# Solder_Paste_Controller.net
KiCad netlist of a schematic drawn in EAGLE
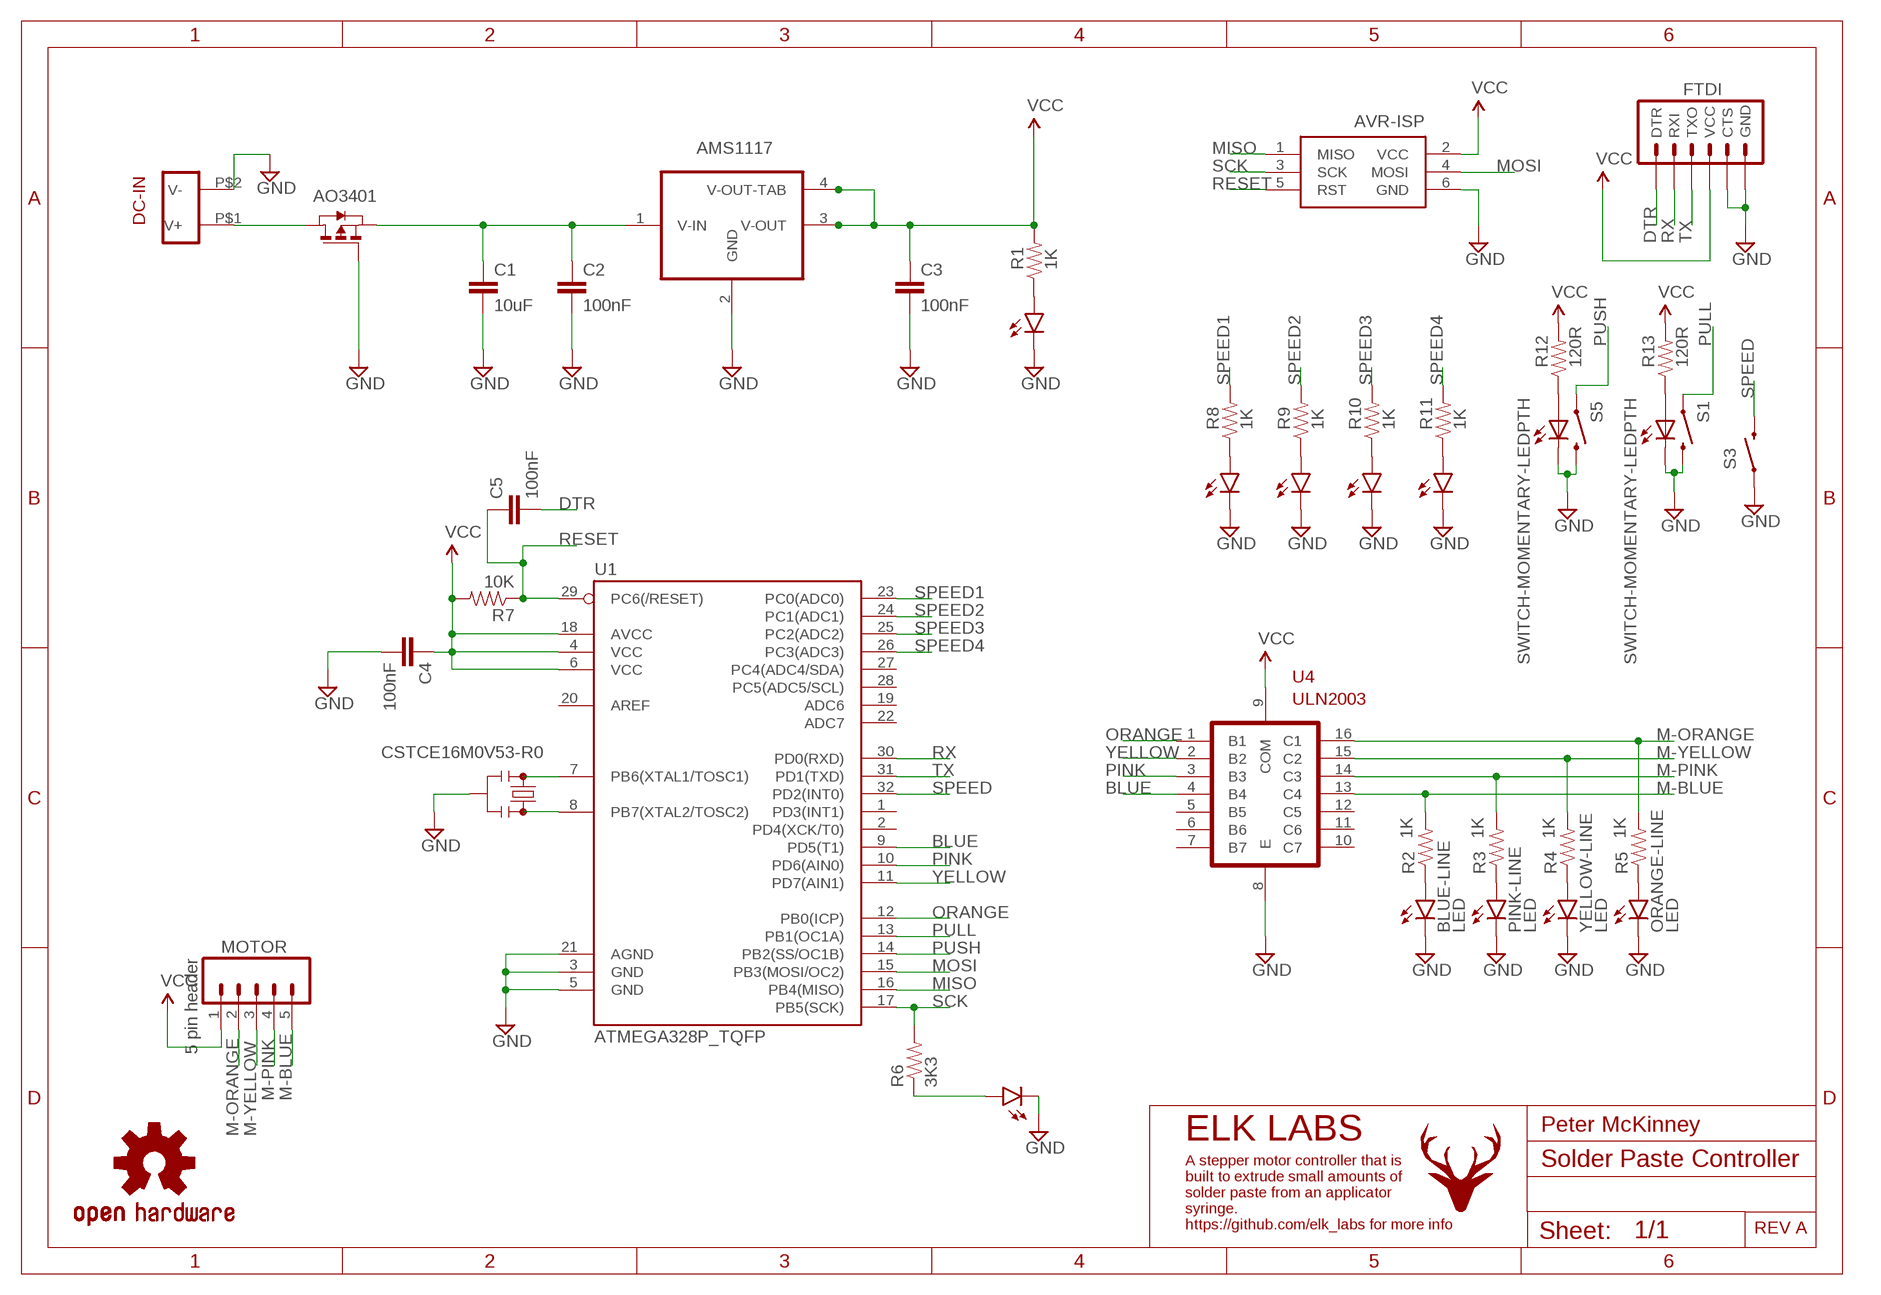
[diagram p0: schematic, sheet 1]

(export (version "E")
  (design (tool "Eeschema 10.0.6"))
  (components
    (comp (ref "AVR-ISP")
      (value "AVRISP-6")
      (footprint "eagle-import:AVRISP")
      (libsource (lib "eagle-import") (part "AVRISP-6"))
    )
    (comp (ref "BLUE-LINE")
      (value "LED")
      (footprint "eagle-import:0805-LED")
      (libsource (lib "eagle-import") (part "LED"))
    )
    (comp (ref "C1")
      (value "10uF")
      (footprint "eagle-import:0805")
      (libsource (lib "eagle-import") (part "1UF-25V-10%(0805)"))
    )
    (comp (ref "C2")
      (value "100nF")
      (footprint "eagle-import:0805")
      (libsource (lib "eagle-import") (part "1UF-25V-10%(0805)"))
    )
    (comp (ref "C3")
      (value "100nF")
      (footprint "eagle-import:0805")
      (libsource (lib "eagle-import") (part "1UF-25V-10%(0805)"))
    )
    (comp (ref "C4")
      (value "100nF")
      (footprint "eagle-import:0805")
      (libsource (lib "eagle-import") (part "1UF-25V-10%(0805)"))
    )
    (comp (ref "C5")
      (value "100nF")
      (footprint "eagle-import:0805")
      (libsource (lib "eagle-import") (part "1UF-25V-10%(0805)"))
    )
    (comp (ref "CRYSTAL")
      (value "CSTCE16M0V53-R0")
      (footprint "eagle-import:CSTCE_V")
      (libsource (lib "eagle-import") (part "CSTCE16M0V53-R0"))
    )
    (comp (ref "DC-IN")
      (value "red black twister wire")
      (footprint "eagle-import:POWER_CONNECTOR_WITH_RELIEF")
      (libsource (lib "eagle-import") (part "POWER-IN-WITH-RELIEF"))
    )
    (comp (ref "FTDI")
      (value "6 pin header")
      (footprint "eagle-import:1X06")
      (libsource (lib "eagle-import") (part "ARDUINO_SERIAL_PROGRAMPTH"))
    )
    (comp (ref "HEARTBEAT")
      (value "LED")
      (footprint "eagle-import:0805-LED")
      (libsource (lib "eagle-import") (part "LED"))
    )
    (comp (ref "LOGO1")
      (value "OSHW-LOGOS")
      (footprint "eagle-import:OSHW-LOGO-S")
      (libsource (lib "eagle-import") (part "OSHW-LOGOS"))
    )
    (comp (ref "MOTOR")
      (value "5 pin header")
      (footprint "eagle-import:1X05")
      (libsource (lib "eagle-import") (part "M05PTH"))
    )
    (comp (ref "ORANGE-LINE")
      (value "LED")
      (footprint "eagle-import:0805-LED")
      (libsource (lib "eagle-import") (part "LED"))
    )
    (comp (ref "PINK-LINE")
      (value "LED")
      (footprint "eagle-import:0805-LED")
      (libsource (lib "eagle-import") (part "LED"))
    )
    (comp (ref "PWRLED")
      (value "LED")
      (footprint "eagle-import:0805-LED")
      (libsource (lib "eagle-import") (part "LED"))
    )
    (comp (ref "R1")
      (value "1K")
      (footprint "eagle-import:0805")
      (libsource (lib "eagle-import") (part "RESISTOR0805-RES"))
    )
    (comp (ref "R2")
      (value "1K")
      (footprint "eagle-import:0805")
      (libsource (lib "eagle-import") (part "RESISTOR0805-RES"))
    )
    (comp (ref "R3")
      (value "1K")
      (footprint "eagle-import:0805")
      (libsource (lib "eagle-import") (part "RESISTOR0805-RES"))
    )
    (comp (ref "R4")
      (value "1K")
      (footprint "eagle-import:0805")
      (libsource (lib "eagle-import") (part "RESISTOR0805-RES"))
    )
    (comp (ref "R5")
      (value "1K")
      (footprint "eagle-import:0805")
      (libsource (lib "eagle-import") (part "RESISTOR0805-RES"))
    )
    (comp (ref "R6")
      (value "3K3")
      (footprint "eagle-import:0805")
      (libsource (lib "eagle-import") (part "RESISTOR0805-RES"))
    )
    (comp (ref "R7")
      (value "10K")
      (footprint "eagle-import:0805")
      (libsource (lib "eagle-import") (part "RESISTOR0805-RES"))
    )
    (comp (ref "R8")
      (value "1K")
      (footprint "eagle-import:0805")
      (libsource (lib "eagle-import") (part "RESISTOR0805-RES"))
    )
    (comp (ref "R9")
      (value "1K")
      (footprint "eagle-import:0805")
      (libsource (lib "eagle-import") (part "RESISTOR0805-RES"))
    )
    (comp (ref "R10")
      (value "1K")
      (footprint "eagle-import:0805")
      (libsource (lib "eagle-import") (part "RESISTOR0805-RES"))
    )
    (comp (ref "R11")
      (value "1K")
      (footprint "eagle-import:0805")
      (libsource (lib "eagle-import") (part "RESISTOR0805-RES"))
    )
    (comp (ref "R12")
      (value "120R")
      (footprint "eagle-import:0805")
      (libsource (lib "eagle-import") (part "RESISTOR0805-RES"))
    )
    (comp (ref "R13")
      (value "120R")
      (footprint "eagle-import:0805")
      (libsource (lib "eagle-import") (part "RESISTOR0805-RES"))
    )
    (comp (ref "S1")
      (value "SWITCH-MOMENTARY-LEDPTH")
      (footprint "eagle-import:TACTILE-PTH-LED-12MM")
      (libsource (lib "eagle-import") (part "SWITCH-MOMENTARY-LEDPTH"))
    )
    (comp (ref "S3")
      (value "SWITCH-MOMENTARY-2SMD-1101NE")
      (footprint "eagle-import:TACTILE-SWITCH-1101NE")
      (libsource (lib "eagle-import") (part "SWITCH-MOMENTARY-2SMD-1101NE"))
    )
    (comp (ref "S5")
      (value "SWITCH-MOMENTARY-LEDPTH")
      (footprint "eagle-import:TACTILE-PTH-LED-12MM")
      (libsource (lib "eagle-import") (part "SWITCH-MOMENTARY-LEDPTH"))
    )
    (comp (ref "SPEED1LED")
      (value "LED")
      (footprint "eagle-import:0805-LED")
      (libsource (lib "eagle-import") (part "LED"))
    )
    (comp (ref "SPEED2LED")
      (value "LED")
      (footprint "eagle-import:0805-LED")
      (libsource (lib "eagle-import") (part "LED"))
    )
    (comp (ref "SPEED3LED")
      (value "LED")
      (footprint "eagle-import:0805-LED")
      (libsource (lib "eagle-import") (part "LED"))
    )
    (comp (ref "SPEED4LED")
      (value "LED")
      (footprint "eagle-import:0805-LED")
      (libsource (lib "eagle-import") (part "LED"))
    )
    (comp (ref "U$1")
      (value "ELK-LOGO")
      (footprint "eagle-import:ELK-LOGO")
      (libsource (lib "eagle-import") (part "ELK-LOGO"))
    )
    (comp (ref "U1")
      (value "ATMEGA328P_TQFP")
      (footprint "eagle-import:TQFP32-08")
      (libsource (lib "eagle-import") (part "ATMEGA328P_TQFP"))
    )
    (comp (ref "U2")
      (value "AMS1117")
      (footprint "eagle-import:SOT-223")
      (libsource (lib "eagle-import") (part "AMS1117"))
    )
    (comp (ref "U3")
      (value "AO3401")
      (footprint "eagle-import:SOT-23")
      (libsource (lib "eagle-import") (part "AO3401"))
    )
    (comp (ref "U4")
      (value "ULN2003")
      (footprint "eagle-import:SOP-16")
      (libsource (lib "eagle-import") (part "ULN2003"))
    )
    (comp (ref "YELLOW-LINE")
      (value "LED")
      (footprint "eagle-import:0805-LED")
      (libsource (lib "eagle-import") (part "LED"))
    )
  )
  (nets
    (net (code "1") (name "/BLUE") (class "Default")
      (node (ref "U1") (pin "9") (pinfunction "PD5(T1)_9") (pintype "bidirectional"))
      (node (ref "U4") (pin "4") (pinfunction "B4_4") (pintype "bidirectional"))
    )
    (net (code "2") (name "/DTR") (class "Default")
      (node (ref "C5") (pin "2") (pinfunction "2_2") (pintype "passive"))
      (node (ref "FTDI") (pin "1") (pinfunction "DTR_1") (pintype "passive"))
    )
    (net (code "3") (name "/M-BLUE") (class "Default")
      (node (ref "MOTOR") (pin "5") (pinfunction "5_5") (pintype "passive"))
      (node (ref "R2") (pin "2") (pinfunction "2_2") (pintype "passive"))
      (node (ref "U4") (pin "13") (pinfunction "C4_13") (pintype "bidirectional"))
    )
    (net (code "4") (name "/M-ORANGE") (class "Default")
      (node (ref "MOTOR") (pin "2") (pinfunction "2_2") (pintype "passive"))
      (node (ref "R5") (pin "2") (pinfunction "2_2") (pintype "passive"))
      (node (ref "U4") (pin "16") (pinfunction "C1_16") (pintype "bidirectional"))
    )
    (net (code "5") (name "/M-PINK") (class "Default")
      (node (ref "MOTOR") (pin "4") (pinfunction "4_4") (pintype "passive"))
      (node (ref "R3") (pin "2") (pinfunction "2_2") (pintype "passive"))
      (node (ref "U4") (pin "14") (pinfunction "C3_14") (pintype "bidirectional"))
    )
    (net (code "6") (name "/M-YELLOW") (class "Default")
      (node (ref "MOTOR") (pin "3") (pinfunction "3_3") (pintype "passive"))
      (node (ref "R4") (pin "2") (pinfunction "2_2") (pintype "passive"))
      (node (ref "U4") (pin "15") (pinfunction "C2_15") (pintype "bidirectional"))
    )
    (net (code "7") (name "/MISO") (class "Default")
      (node (ref "AVR-ISP") (pin "1") (pinfunction "MISO_1") (pintype "input"))
      (node (ref "U1") (pin "16") (pinfunction "PB4(MISO)_16") (pintype "bidirectional"))
    )
    (net (code "8") (name "/MOSI") (class "Default")
      (node (ref "AVR-ISP") (pin "4") (pinfunction "MOSI_4") (pintype "output"))
      (node (ref "U1") (pin "15") (pinfunction "PB3(MOSI/OC2)_15") (pintype "bidirectional"))
    )
    (net (code "9") (name "/ORANGE") (class "Default")
      (node (ref "U1") (pin "12") (pinfunction "PB0(ICP)_12") (pintype "bidirectional"))
      (node (ref "U4") (pin "1") (pinfunction "B1_1") (pintype "bidirectional"))
    )
    (net (code "10") (name "/PINK") (class "Default")
      (node (ref "U1") (pin "10") (pinfunction "PD6(AIN0)_10") (pintype "bidirectional"))
      (node (ref "U4") (pin "3") (pinfunction "B3_3") (pintype "bidirectional"))
    )
    (net (code "11") (name "/PULL") (class "Default")
      (node (ref "S1") (pin "4") (pinfunction "1_4") (pintype "passive"))
      (node (ref "U1") (pin "13") (pinfunction "PB1(OC1A)_13") (pintype "bidirectional"))
    )
    (net (code "12") (name "/PUSH") (class "Default")
      (node (ref "S5") (pin "4") (pinfunction "1_4") (pintype "passive"))
      (node (ref "U1") (pin "14") (pinfunction "PB2(SS/OC1B)_14") (pintype "bidirectional"))
    )
    (net (code "13") (name "/RESET") (class "Default")
      (node (ref "AVR-ISP") (pin "5") (pinfunction "RST_5") (pintype "output"))
      (node (ref "C5") (pin "1") (pinfunction "1_1") (pintype "passive"))
      (node (ref "R7") (pin "1") (pinfunction "1_1") (pintype "passive"))
      (node (ref "U1") (pin "29") (pinfunction "PC6(/RESET)_29") (pintype "bidirectional"))
    )
    (net (code "14") (name "/RX") (class "Default")
      (node (ref "FTDI") (pin "2") (pinfunction "RXI_2") (pintype "passive"))
      (node (ref "U1") (pin "30") (pinfunction "PD0(RXD)_30") (pintype "bidirectional"))
    )
    (net (code "15") (name "/SCK") (class "Default")
      (node (ref "AVR-ISP") (pin "3") (pinfunction "SCK_3") (pintype "output"))
      (node (ref "R6") (pin "2") (pinfunction "2_2") (pintype "passive"))
      (node (ref "U1") (pin "17") (pinfunction "PB5(SCK)_17") (pintype "bidirectional"))
    )
    (net (code "16") (name "/SPEED") (class "Default")
      (node (ref "S3") (pin "2") (pinfunction "2_2") (pintype "passive"))
      (node (ref "U1") (pin "32") (pinfunction "PD2(INT0)_32") (pintype "bidirectional"))
    )
    (net (code "17") (name "/SPEED1") (class "Default")
      (node (ref "R8") (pin "2") (pinfunction "2_2") (pintype "passive"))
      (node (ref "U1") (pin "23") (pinfunction "PC0(ADC0)_23") (pintype "bidirectional"))
    )
    (net (code "18") (name "/SPEED2") (class "Default")
      (node (ref "R9") (pin "2") (pinfunction "2_2") (pintype "passive"))
      (node (ref "U1") (pin "24") (pinfunction "PC1(ADC1)_24") (pintype "bidirectional"))
    )
    (net (code "19") (name "/SPEED3") (class "Default")
      (node (ref "R10") (pin "2") (pinfunction "2_2") (pintype "passive"))
      (node (ref "U1") (pin "25") (pinfunction "PC2(ADC2)_25") (pintype "bidirectional"))
    )
    (net (code "20") (name "/SPEED4") (class "Default")
      (node (ref "R11") (pin "2") (pinfunction "2_2") (pintype "passive"))
      (node (ref "U1") (pin "26") (pinfunction "PC3(ADC3)_26") (pintype "bidirectional"))
    )
    (net (code "21") (name "/TX") (class "Default")
      (node (ref "FTDI") (pin "3") (pinfunction "TXO_3") (pintype "passive"))
      (node (ref "U1") (pin "31") (pinfunction "PD1(TXD)_31") (pintype "bidirectional"))
    )
    (net (code "22") (name "/YELLOW") (class "Default")
      (node (ref "U1") (pin "11") (pinfunction "PD7(AIN1)_11") (pintype "bidirectional"))
      (node (ref "U4") (pin "2") (pinfunction "B2_2") (pintype "bidirectional"))
    )
    (net (code "23") (name "GND") (class "Default")
      (node (ref "AVR-ISP") (pin "6") (pinfunction "GND_6") (pintype "power_in"))
      (node (ref "BLUE-LINE") (pin "C") (pinfunction "C_C") (pintype "passive"))
      (node (ref "C1") (pin "2") (pinfunction "2_2") (pintype "passive"))
      (node (ref "C2") (pin "2") (pinfunction "2_2") (pintype "passive"))
      (node (ref "C3") (pin "2") (pinfunction "2_2") (pintype "passive"))
      (node (ref "C4") (pin "2") (pinfunction "2_2") (pintype "passive"))
      (node (ref "CRYSTAL") (pin "GND") (pinfunction "GND_GND") (pintype "passive"))
      (node (ref "DC-IN") (pin "P$2") (pinfunction "V-_P$2") (pintype "bidirectional"))
      (node (ref "FTDI") (pin "5") (pinfunction "CTS_5") (pintype "passive"))
      (node (ref "FTDI") (pin "6") (pinfunction "GND_6") (pintype "passive"))
      (node (ref "HEARTBEAT") (pin "C") (pinfunction "C_C") (pintype "passive"))
      (node (ref "ORANGE-LINE") (pin "C") (pinfunction "C_C") (pintype "passive"))
      (node (ref "PINK-LINE") (pin "C") (pinfunction "C_C") (pintype "passive"))
      (node (ref "PWRLED") (pin "C") (pinfunction "C_C") (pintype "passive"))
      (node (ref "S1") (pin "2") (pinfunction "2_2") (pintype "passive"))
      (node (ref "S1") (pin "C") (pinfunction "C_C") (pintype "passive"))
      (node (ref "S3") (pin "1") (pinfunction "1_1") (pintype "passive"))
      (node (ref "S5") (pin "2") (pinfunction "2_2") (pintype "passive"))
      (node (ref "S5") (pin "C") (pinfunction "C_C") (pintype "passive"))
      (node (ref "SPEED1LED") (pin "C") (pinfunction "C_C") (pintype "passive"))
      (node (ref "SPEED2LED") (pin "C") (pinfunction "C_C") (pintype "passive"))
      (node (ref "SPEED3LED") (pin "C") (pinfunction "C_C") (pintype "passive"))
      (node (ref "SPEED4LED") (pin "C") (pinfunction "C_C") (pintype "passive"))
      (node (ref "U1") (pin "21") (pinfunction "AGND_21") (pintype "bidirectional"))
      (node (ref "U1") (pin "3") (pinfunction "GND_3") (pintype "bidirectional"))
      (node (ref "U1") (pin "5") (pinfunction "GND_5") (pintype "bidirectional"))
      (node (ref "U2") (pin "2") (pinfunction "GND_2") (pintype "bidirectional"))
      (node (ref "U3") (pin "1") (pinfunction "G_1") (pintype "passive"))
      (node (ref "U4") (pin "8") (pinfunction "E_8") (pintype "bidirectional"))
      (node (ref "YELLOW-LINE") (pin "C") (pinfunction "C_C") (pintype "passive"))
    )
    (net (code "24") (name "Net-(BLUE-LINE-PadA)") (class "Default")
      (node (ref "BLUE-LINE") (pin "A") (pinfunction "A_A") (pintype "passive"))
      (node (ref "R2") (pin "1") (pinfunction "1_1") (pintype "passive"))
    )
    (net (code "25") (name "Net-(DC-IN-V+)") (class "Default")
      (node (ref "DC-IN") (pin "P$1") (pinfunction "V+_P$1") (pintype "bidirectional"))
      (node (ref "U3") (pin "3") (pinfunction "D_3") (pintype "passive"))
    )
    (net (code "26") (name "Net-(HEARTBEAT-PadA)") (class "Default")
      (node (ref "HEARTBEAT") (pin "A") (pinfunction "A_A") (pintype "passive"))
      (node (ref "R6") (pin "1") (pinfunction "1_1") (pintype "passive"))
    )
    (net (code "27") (name "Net-(ORANGE-LINE-PadA)") (class "Default")
      (node (ref "ORANGE-LINE") (pin "A") (pinfunction "A_A") (pintype "passive"))
      (node (ref "R5") (pin "1") (pinfunction "1_1") (pintype "passive"))
    )
    (net (code "28") (name "Net-(PINK-LINE-PadA)") (class "Default")
      (node (ref "PINK-LINE") (pin "A") (pinfunction "A_A") (pintype "passive"))
      (node (ref "R3") (pin "1") (pinfunction "1_1") (pintype "passive"))
    )
    (net (code "29") (name "Net-(PWRLED-PadA)") (class "Default")
      (node (ref "PWRLED") (pin "A") (pinfunction "A_A") (pintype "passive"))
      (node (ref "R1") (pin "1") (pinfunction "1_1") (pintype "passive"))
    )
    (net (code "30") (name "Net-(R4-Pad1)") (class "Default")
      (node (ref "R4") (pin "1") (pinfunction "1_1") (pintype "passive"))
      (node (ref "YELLOW-LINE") (pin "A") (pinfunction "A_A") (pintype "passive"))
    )
    (net (code "31") (name "Net-(R8-Pad1)") (class "Default")
      (node (ref "R8") (pin "1") (pinfunction "1_1") (pintype "passive"))
      (node (ref "SPEED1LED") (pin "A") (pinfunction "A_A") (pintype "passive"))
    )
    (net (code "32") (name "Net-(R9-Pad1)") (class "Default")
      (node (ref "R9") (pin "1") (pinfunction "1_1") (pintype "passive"))
      (node (ref "SPEED2LED") (pin "A") (pinfunction "A_A") (pintype "passive"))
    )
    (net (code "33") (name "Net-(R10-Pad1)") (class "Default")
      (node (ref "R10") (pin "1") (pinfunction "1_1") (pintype "passive"))
      (node (ref "SPEED3LED") (pin "A") (pinfunction "A_A") (pintype "passive"))
    )
    (net (code "34") (name "Net-(R11-Pad1)") (class "Default")
      (node (ref "R11") (pin "1") (pinfunction "1_1") (pintype "passive"))
      (node (ref "SPEED4LED") (pin "A") (pinfunction "A_A") (pintype "passive"))
    )
    (net (code "35") (name "Net-(R12-Pad1)") (class "Default")
      (node (ref "R12") (pin "1") (pinfunction "1_1") (pintype "passive"))
      (node (ref "S5") (pin "A") (pinfunction "A_A") (pintype "passive"))
    )
    (net (code "36") (name "Net-(R13-Pad1)") (class "Default")
      (node (ref "R13") (pin "1") (pinfunction "1_1") (pintype "passive"))
      (node (ref "S1") (pin "A") (pinfunction "A_A") (pintype "passive"))
    )
    (net (code "37") (name "Net-(U1-PB6(XTAL1{slash}TOSC1))") (class "Default")
      (node (ref "CRYSTAL") (pin "1") (pinfunction "1_1") (pintype "passive"))
      (node (ref "U1") (pin "7") (pinfunction "PB6(XTAL1/TOSC1)_7") (pintype "bidirectional"))
    )
    (net (code "38") (name "Net-(U1-PB7(XTAL2{slash}TOSC2))") (class "Default")
      (node (ref "CRYSTAL") (pin "3") (pinfunction "3_3") (pintype "passive"))
      (node (ref "U1") (pin "8") (pinfunction "PB7(XTAL2/TOSC2)_8") (pintype "bidirectional"))
    )
    (net (code "39") (name "Net-(U2-V-IN)") (class "Default")
      (node (ref "C1") (pin "1") (pinfunction "1_1") (pintype "passive"))
      (node (ref "C2") (pin "1") (pinfunction "1_1") (pintype "passive"))
      (node (ref "U2") (pin "1") (pinfunction "V-IN_1") (pintype "bidirectional"))
      (node (ref "U3") (pin "2") (pinfunction "S_2") (pintype "passive"))
    )
    (net (code "40") (name "VCC") (class "Default")
      (node (ref "AVR-ISP") (pin "2") (pinfunction "VCC_2") (pintype "power_in"))
      (node (ref "C3") (pin "1") (pinfunction "1_1") (pintype "passive"))
      (node (ref "C4") (pin "1") (pinfunction "1_1") (pintype "passive"))
      (node (ref "FTDI") (pin "4") (pinfunction "VCC_4") (pintype "passive"))
      (node (ref "MOTOR") (pin "1") (pinfunction "1_1") (pintype "passive"))
      (node (ref "R1") (pin "2") (pinfunction "2_2") (pintype "passive"))
      (node (ref "R12") (pin "2") (pinfunction "2_2") (pintype "passive"))
      (node (ref "R13") (pin "2") (pinfunction "2_2") (pintype "passive"))
      (node (ref "R7") (pin "2") (pinfunction "2_2") (pintype "passive"))
      (node (ref "U1") (pin "18") (pinfunction "AVCC_18") (pintype "bidirectional"))
      (node (ref "U1") (pin "4") (pinfunction "VCC_4") (pintype "bidirectional"))
      (node (ref "U1") (pin "6") (pinfunction "VCC_6") (pintype "bidirectional"))
      (node (ref "U2") (pin "3") (pinfunction "V-OUT_3") (pintype "bidirectional"))
      (node (ref "U2") (pin "4") (pinfunction "V-OUT-TAB_4") (pintype "bidirectional"))
      (node (ref "U4") (pin "9") (pinfunction "COM_9") (pintype "bidirectional"))
    )
    (net (code "41") (name "unconnected-(U1-ADC6-Pad19)") (class "Default")
      (node (ref "U1") (pin "19") (pinfunction "ADC6_19") (pintype "bidirectional"))
    )
    (net (code "42") (name "unconnected-(U1-ADC7-Pad22)") (class "Default")
      (node (ref "U1") (pin "22") (pinfunction "ADC7_22") (pintype "bidirectional"))
    )
    (net (code "43") (name "unconnected-(U1-AREF-Pad20)") (class "Default")
      (node (ref "U1") (pin "20") (pinfunction "AREF_20") (pintype "bidirectional"))
    )
    (net (code "44") (name "unconnected-(U1-PC4(ADC4{slash}SDA)-Pad27)") (class "Default")
      (node (ref "U1") (pin "27") (pinfunction "PC4(ADC4/SDA)_27") (pintype "bidirectional"))
    )
    (net (code "45") (name "unconnected-(U1-PC5(ADC5{slash}SCL)-Pad28)") (class "Default")
      (node (ref "U1") (pin "28") (pinfunction "PC5(ADC5/SCL)_28") (pintype "bidirectional"))
    )
    (net (code "46") (name "unconnected-(U1-PD3(INT1)-Pad1)") (class "Default")
      (node (ref "U1") (pin "1") (pinfunction "PD3(INT1)_1") (pintype "bidirectional"))
    )
    (net (code "47") (name "unconnected-(U1-PD4(XCK{slash}T0)-Pad2)") (class "Default")
      (node (ref "U1") (pin "2") (pinfunction "PD4(XCK/T0)_2") (pintype "bidirectional"))
    )
    (net (code "48") (name "unconnected-(U4-B5-Pad5)") (class "Default")
      (node (ref "U4") (pin "5") (pinfunction "B5_5") (pintype "bidirectional"))
    )
    (net (code "49") (name "unconnected-(U4-B6-Pad6)") (class "Default")
      (node (ref "U4") (pin "6") (pinfunction "B6_6") (pintype "bidirectional"))
    )
    (net (code "50") (name "unconnected-(U4-B7-Pad7)") (class "Default")
      (node (ref "U4") (pin "7") (pinfunction "B7_7") (pintype "bidirectional"))
    )
    (net (code "51") (name "unconnected-(U4-C5-Pad12)") (class "Default")
      (node (ref "U4") (pin "12") (pinfunction "C5_12") (pintype "bidirectional"))
    )
    (net (code "52") (name "unconnected-(U4-C6-Pad11)") (class "Default")
      (node (ref "U4") (pin "11") (pinfunction "C6_11") (pintype "bidirectional"))
    )
    (net (code "53") (name "unconnected-(U4-C7-Pad10)") (class "Default")
      (node (ref "U4") (pin "10") (pinfunction "C7_10") (pintype "bidirectional"))
    )
  )
)
